# gemini.net
KiCad netlist of a schematic drawn in EAGLE
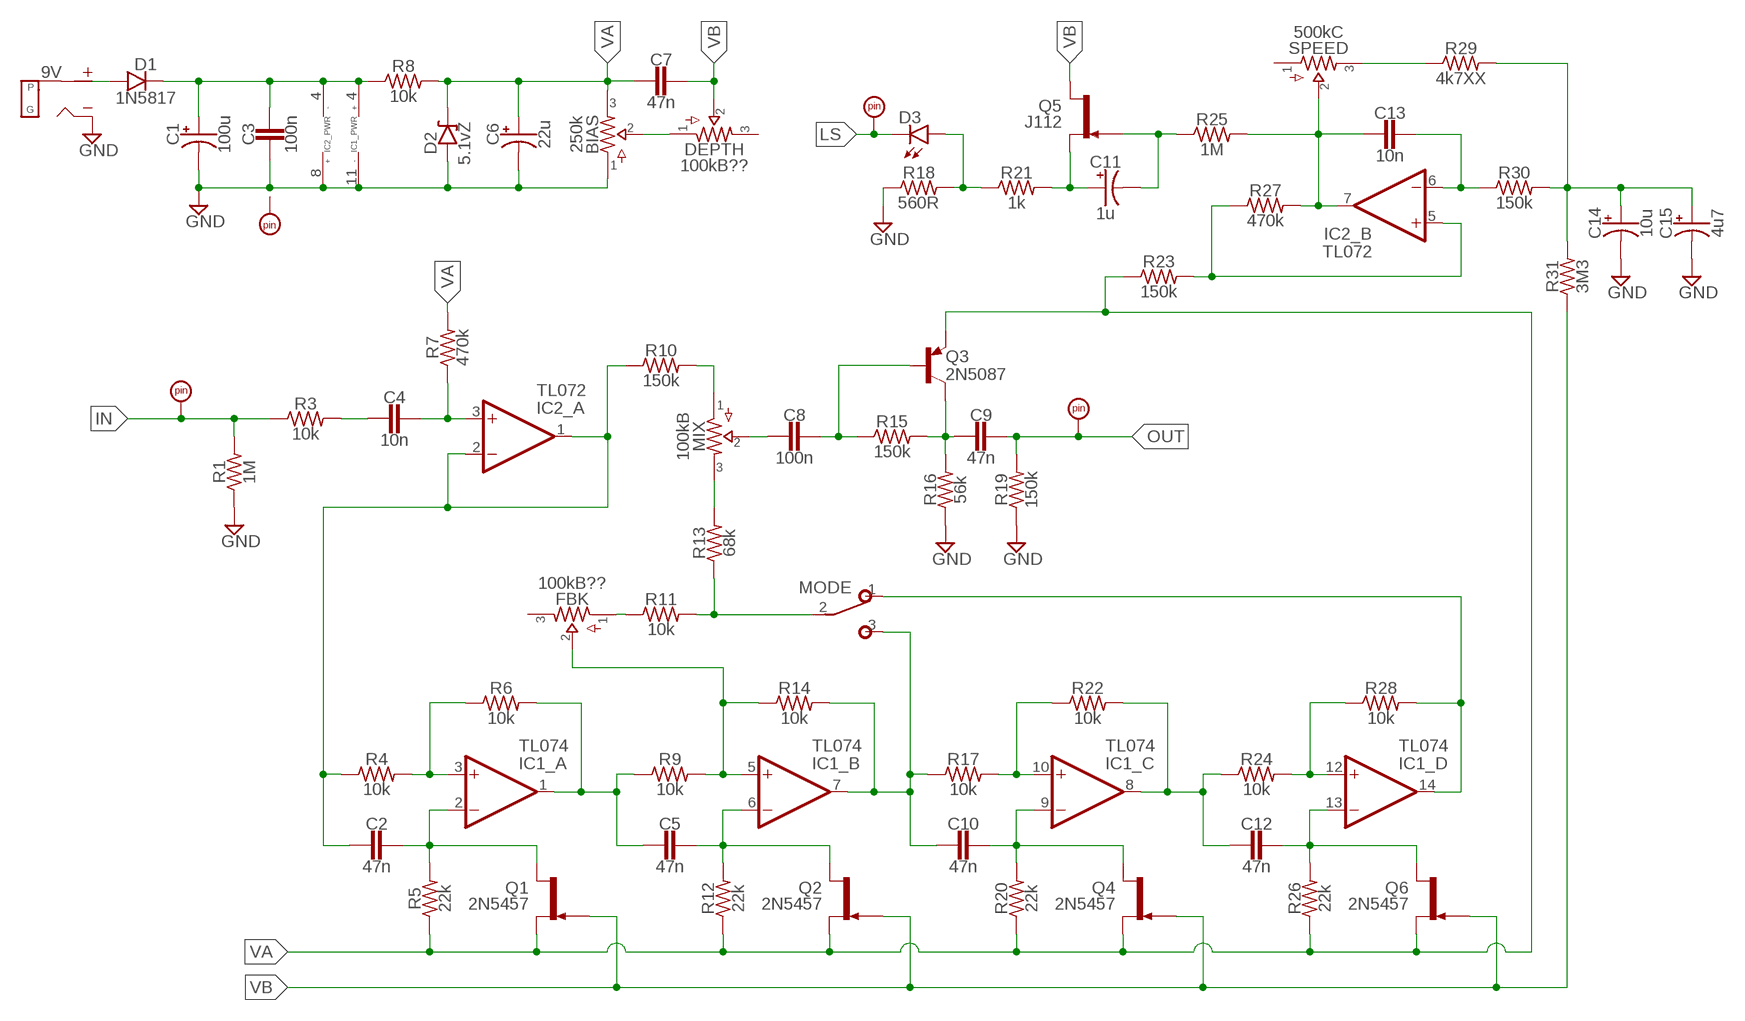
[diagram p0: schematic, sheet 1]

(export (version "E")
  (design (tool "Eeschema 10.0.6"))
  (components
    (comp (ref "9V")
      (value "DC_MONO")
      (footprint "eagle-import:DC")
      (libsource (lib "eagle-import") (part "DC_MONO"))
    )
    (comp (ref "BIAS")
      (value "250k")
      (footprint "eagle-import:2262_TRIM")
      (libsource (lib "eagle-import") (part "POTSTRIM"))
    )
    (comp (ref "C1")
      (value "100u")
      (footprint "eagle-import:050_020_1")
      (libsource (lib "eagle-import") (part "0501"))
    )
    (comp (ref "C2")
      (value "47n")
      (footprint "eagle-import:050X030_025_2")
      (libsource (lib "eagle-import") (part "CER/FILM2"))
    )
    (comp (ref "C3")
      (value "100n")
      (footprint "eagle-import:050X030_025_2")
      (libsource (lib "eagle-import") (part "CER/FILM2"))
    )
    (comp (ref "C4")
      (value "10n")
      (footprint "eagle-import:050X030_025_2")
      (libsource (lib "eagle-import") (part "CER/FILM2"))
    )
    (comp (ref "C5")
      (value "47n")
      (footprint "eagle-import:050X030_025_2")
      (libsource (lib "eagle-import") (part "CER/FILM2"))
    )
    (comp (ref "C6")
      (value "22u")
      (footprint "eagle-import:050_020_1")
      (libsource (lib "eagle-import") (part "0501"))
    )
    (comp (ref "C7")
      (value "47n")
      (footprint "eagle-import:050X030_025_2")
      (libsource (lib "eagle-import") (part "CER/FILM2"))
    )
    (comp (ref "C8")
      (value "100n")
      (footprint "eagle-import:050X030_025_2")
      (libsource (lib "eagle-import") (part "CER/FILM2"))
    )
    (comp (ref "C9")
      (value "47n")
      (footprint "eagle-import:050X030_025_2")
      (libsource (lib "eagle-import") (part "CER/FILM2"))
    )
    (comp (ref "C10")
      (value "47n")
      (footprint "eagle-import:050X030_025_2")
      (libsource (lib "eagle-import") (part "CER/FILM2"))
    )
    (comp (ref "C11")
      (value "1u")
      (footprint "eagle-import:050_020_1")
      (libsource (lib "eagle-import") (part "0501"))
    )
    (comp (ref "C12")
      (value "47n")
      (footprint "eagle-import:050X030_025_2")
      (libsource (lib "eagle-import") (part "CER/FILM2"))
    )
    (comp (ref "C13")
      (value "10n")
      (footprint "eagle-import:050X030_025_2")
      (libsource (lib "eagle-import") (part "CER/FILM2"))
    )
    (comp (ref "C14")
      (value "10u")
      (footprint "eagle-import:050_020_1")
      (libsource (lib "eagle-import") (part "0501"))
    )
    (comp (ref "C15")
      (value "4u7")
      (footprint "eagle-import:050_020_1")
      (libsource (lib "eagle-import") (part "0501"))
    )
    (comp (ref "D1")
      (value "1N5817")
      (footprint "eagle-import:DO41-2")
      (libsource (lib "eagle-import") (part "DO41.2"))
    )
    (comp (ref "D2")
      (value "5.1vZ")
      (footprint "eagle-import:DO41-3")
      (libsource (lib "eagle-import") (part "ZENER.3"))
    )
    (comp (ref "D3")
      (value "LEDA")
      (footprint "eagle-import:3MM_A")
      (libsource (lib "eagle-import") (part "LEDA"))
    )
    (comp (ref "DEPTH")
      (value "100kB??")
      (footprint "eagle-import:16MM")
      (libsource (lib "eagle-import") (part "POTS16MM"))
    )
    (comp (ref "FBK")
      (value "100kB??")
      (footprint "eagle-import:16MM")
      (libsource (lib "eagle-import") (part "POTS16MM"))
    )
    (comp (ref "GND")
      (value "PADRND")
      (footprint "eagle-import:ROUND")
      (libsource (lib "eagle-import") (part "PADRND"))
    )
    (comp (ref "IC1")
      (value "TL074")
      (footprint "eagle-import:DIL14")
      (libsource (lib "eagle-import") (part "QUADTH"))
    )
    (comp (ref "IC2")
      (value "TL072")
      (footprint "eagle-import:DIL08")
      (libsource (lib "eagle-import") (part "DUALTH"))
    )
    (comp (ref "IN")
      (value "PADSQR")
      (footprint "eagle-import:SQUARE")
      (libsource (lib "eagle-import") (part "PADSQR"))
    )
    (comp (ref "MIX")
      (value "100kB")
      (footprint "eagle-import:16MM")
      (libsource (lib "eagle-import") (part "POTS16MM"))
    )
    (comp (ref "MODE")
      (value "SPDTPADS")
      (footprint "eagle-import:SPDT")
      (libsource (lib "eagle-import") (part "SPDTPADS"))
    )
    (comp (ref "OUT")
      (value "PADSQR")
      (footprint "eagle-import:SQUARE")
      (libsource (lib "eagle-import") (part "PADSQR"))
    )
    (comp (ref "PAD3")
      (value "PADRND")
      (footprint "eagle-import:ROUND")
      (libsource (lib "eagle-import") (part "PADRND"))
    )
    (comp (ref "Q1")
      (value "2N5457")
      (footprint "eagle-import:TO92-")
      (libsource (lib "eagle-import") (part "2N5457"))
    )
    (comp (ref "Q2")
      (value "2N5457")
      (footprint "eagle-import:TO92-")
      (libsource (lib "eagle-import") (part "2N5457"))
    )
    (comp (ref "Q3")
      (value "2N5087")
      (footprint "eagle-import:TO92-")
      (libsource (lib "eagle-import") (part "2N5087.1"))
    )
    (comp (ref "Q4")
      (value "2N5457")
      (footprint "eagle-import:TO92-")
      (libsource (lib "eagle-import") (part "2N5457"))
    )
    (comp (ref "Q5")
      (value "J112")
      (footprint "eagle-import:TO92-")
      (libsource (lib "eagle-import") (part "J201"))
    )
    (comp (ref "Q6")
      (value "2N5457")
      (footprint "eagle-import:TO92-")
      (libsource (lib "eagle-import") (part "2N5457"))
    )
    (comp (ref "R1")
      (value "1M")
      (footprint "eagle-import:R0207_3")
      (libsource (lib "eagle-import") (part "R_.3B"))
    )
    (comp (ref "R3")
      (value "10k")
      (footprint "eagle-import:R0207_3")
      (libsource (lib "eagle-import") (part "R_.3B"))
    )
    (comp (ref "R4")
      (value "10k")
      (footprint "eagle-import:R0207_3")
      (libsource (lib "eagle-import") (part "R_.3B"))
    )
    (comp (ref "R5")
      (value "22k")
      (footprint "eagle-import:R0207_3")
      (libsource (lib "eagle-import") (part "R_.3B"))
    )
    (comp (ref "R6")
      (value "10k")
      (footprint "eagle-import:R0207_3")
      (libsource (lib "eagle-import") (part "R_.3B"))
    )
    (comp (ref "R7")
      (value "470k")
      (footprint "eagle-import:R0207_3")
      (libsource (lib "eagle-import") (part "R_.3B"))
    )
    (comp (ref "R8")
      (value "10k")
      (footprint "eagle-import:R0207_3")
      (libsource (lib "eagle-import") (part "R_.3B"))
    )
    (comp (ref "R9")
      (value "10k")
      (footprint "eagle-import:R0207_3")
      (libsource (lib "eagle-import") (part "R_.3B"))
    )
    (comp (ref "R10")
      (value "150k")
      (footprint "eagle-import:R0207_3")
      (libsource (lib "eagle-import") (part "R_.3B"))
    )
    (comp (ref "R11")
      (value "10k")
      (footprint "eagle-import:R0207_3")
      (libsource (lib "eagle-import") (part "R_.3B"))
    )
    (comp (ref "R12")
      (value "22k")
      (footprint "eagle-import:R0207_3")
      (libsource (lib "eagle-import") (part "R_.3B"))
    )
    (comp (ref "R13")
      (value "68k")
      (footprint "eagle-import:R0207_3")
      (libsource (lib "eagle-import") (part "R_.3B"))
    )
    (comp (ref "R14")
      (value "10k")
      (footprint "eagle-import:R0207_3")
      (libsource (lib "eagle-import") (part "R_.3B"))
    )
    (comp (ref "R15")
      (value "150k")
      (footprint "eagle-import:R0207_3")
      (libsource (lib "eagle-import") (part "R_.3B"))
    )
    (comp (ref "R16")
      (value "56k")
      (footprint "eagle-import:R0207_3")
      (libsource (lib "eagle-import") (part "R_.3B"))
    )
    (comp (ref "R17")
      (value "10k")
      (footprint "eagle-import:R0207_3")
      (libsource (lib "eagle-import") (part "R_.3B"))
    )
    (comp (ref "R18")
      (value "560R")
      (footprint "eagle-import:R0207_3")
      (libsource (lib "eagle-import") (part "R_.3B"))
    )
    (comp (ref "R19")
      (value "150k")
      (footprint "eagle-import:R0207_3")
      (libsource (lib "eagle-import") (part "R_.3B"))
    )
    (comp (ref "R20")
      (value "22k")
      (footprint "eagle-import:R0207_3")
      (libsource (lib "eagle-import") (part "R_.3B"))
    )
    (comp (ref "R21")
      (value "1k")
      (footprint "eagle-import:R0207_3")
      (libsource (lib "eagle-import") (part "R_.3B"))
    )
    (comp (ref "R22")
      (value "10k")
      (footprint "eagle-import:R0207_3")
      (libsource (lib "eagle-import") (part "R_.3B"))
    )
    (comp (ref "R23")
      (value "150k")
      (footprint "eagle-import:R0207_3")
      (libsource (lib "eagle-import") (part "R_.3B"))
    )
    (comp (ref "R24")
      (value "10k")
      (footprint "eagle-import:R0207_3")
      (libsource (lib "eagle-import") (part "R_.3B"))
    )
    (comp (ref "R25")
      (value "1M")
      (footprint "eagle-import:R0207_3")
      (libsource (lib "eagle-import") (part "R_.3B"))
    )
    (comp (ref "R26")
      (value "22k")
      (footprint "eagle-import:R0207_3")
      (libsource (lib "eagle-import") (part "R_.3B"))
    )
    (comp (ref "R27")
      (value "470k")
      (footprint "eagle-import:R0207_3")
      (libsource (lib "eagle-import") (part "R_.3B"))
    )
    (comp (ref "R28")
      (value "10k")
      (footprint "eagle-import:R0207_3")
      (libsource (lib "eagle-import") (part "R_.3B"))
    )
    (comp (ref "R29")
      (value "4k7XX")
      (footprint "eagle-import:R0207_3")
      (libsource (lib "eagle-import") (part "R_.3B"))
    )
    (comp (ref "R30")
      (value "150k")
      (footprint "eagle-import:R0207_3")
      (libsource (lib "eagle-import") (part "R_.3B"))
    )
    (comp (ref "R31")
      (value "3M3")
      (footprint "eagle-import:R0207_3")
      (libsource (lib "eagle-import") (part "R_.3B"))
    )
    (comp (ref "SPEED")
      (value "500kC")
      (footprint "eagle-import:16MM")
      (libsource (lib "eagle-import") (part "POTS16MM"))
    )
  )
  (nets
    (net (code "1") (name "GND") (class "Default")
      (node (ref "9V") (pin "S") (pinfunction "SLEEVE_S") (pintype "passive"))
      (node (ref "BIAS") (pin "1") (pinfunction "1_1") (pintype "passive"))
      (node (ref "C1") (pin "-") (pinfunction "-_-") (pintype "passive"))
      (node (ref "C14") (pin "-") (pinfunction "-_-") (pintype "passive"))
      (node (ref "C15") (pin "-") (pinfunction "-_-") (pintype "passive"))
      (node (ref "C3") (pin "2") (pinfunction "2_2") (pintype "passive"))
      (node (ref "C6") (pin "-") (pinfunction "-_-") (pintype "passive"))
      (node (ref "D2") (pin "A") (pinfunction "A_A") (pintype "passive"))
      (node (ref "IC1") (pin "11") (pinfunction "V-_11") (pintype "power_in"))
      (node (ref "IC2") (pin "8") (pinfunction "V+_8") (pintype "power_in"))
      (node (ref "R1") (pin "1") (pinfunction "1_1") (pintype "passive"))
      (node (ref "R16") (pin "1") (pinfunction "1_1") (pintype "passive"))
      (node (ref "R18") (pin "1") (pinfunction "1_1") (pintype "passive"))
      (node (ref "R19") (pin "1") (pinfunction "1_1") (pintype "passive"))
    )
    (net (code "2") (name "IN") (class "Default")
      (node (ref "IN") (pin "1") (pinfunction "P$1_1") (pintype "bidirectional"))
      (node (ref "R1") (pin "2") (pinfunction "2_2") (pintype "passive"))
      (node (ref "R3") (pin "1") (pinfunction "1_1") (pintype "passive"))
    )
    (net (code "3") (name "LS") (class "Default")
      (node (ref "D3") (pin "K") (pinfunction "C_K") (pintype "passive"))
      (node (ref "PAD3") (pin "1") (pinfunction "P$1_1") (pintype "bidirectional"))
    )
    (net (code "4") (name "Net-(9V-TIP)") (class "Default")
      (node (ref "9V") (pin "T") (pinfunction "TIP_T") (pintype "passive"))
      (node (ref "D1") (pin "A") (pinfunction "A_A") (pintype "passive"))
    )
    (net (code "5") (name "Net-(BIAS-Pad2)") (class "Default")
      (node (ref "BIAS") (pin "2") (pinfunction "2_2") (pintype "passive"))
      (node (ref "DEPTH") (pin "1") (pinfunction "1_1") (pintype "passive"))
    )
    (net (code "6") (name "Net-(C4-Pad2)") (class "Default")
      (node (ref "C4") (pin "2") (pinfunction "2_2") (pintype "passive"))
      (node (ref "R3") (pin "2") (pinfunction "2_2") (pintype "passive"))
    )
    (net (code "7") (name "Net-(C8-Pad2)") (class "Default")
      (node (ref "C8") (pin "2") (pinfunction "2_2") (pintype "passive"))
      (node (ref "MIX") (pin "2") (pinfunction "2_2") (pintype "passive"))
    )
    (net (code "8") (name "Net-(C14-Pad+)") (class "Default")
      (node (ref "C14") (pin "+") (pinfunction "+_+") (pintype "passive"))
      (node (ref "C15") (pin "+") (pinfunction "+_+") (pintype "passive"))
      (node (ref "R29") (pin "2") (pinfunction "2_2") (pintype "passive"))
      (node (ref "R30") (pin "2") (pinfunction "2_2") (pintype "passive"))
      (node (ref "R31") (pin "2") (pinfunction "2_2") (pintype "passive"))
    )
    (net (code "9") (name "Net-(D3-PadA)") (class "Default")
      (node (ref "D3") (pin "A") (pinfunction "A_A") (pintype "passive"))
      (node (ref "R18") (pin "2") (pinfunction "2_2") (pintype "passive"))
      (node (ref "R21") (pin "1") (pinfunction "1_1") (pintype "passive"))
    )
    (net (code "10") (name "Net-(FBK-Pad1)") (class "Default")
      (node (ref "FBK") (pin "1") (pinfunction "1_1") (pintype "passive"))
      (node (ref "R11") (pin "1") (pinfunction "1_1") (pintype "passive"))
    )
    (net (code "11") (name "Net-(IC1A-+IN)") (class "Default")
      (node (ref "IC1") (pin "3") (pinfunction "+IN_3") (pintype "input"))
      (node (ref "R4") (pin "2") (pinfunction "2_2") (pintype "passive"))
      (node (ref "R6") (pin "1") (pinfunction "1_1") (pintype "passive"))
    )
    (net (code "12") (name "Net-(IC1A--IN)") (class "Default")
      (node (ref "C2") (pin "1") (pinfunction "1_1") (pintype "passive"))
      (node (ref "IC1") (pin "2") (pinfunction "-IN_2") (pintype "input"))
      (node (ref "Q1") (pin "3") (pinfunction "D_3") (pintype "passive"))
      (node (ref "R5") (pin "2") (pinfunction "2_2") (pintype "passive"))
    )
    (net (code "13") (name "Net-(IC1A-OUT)") (class "Default")
      (node (ref "C5") (pin "2") (pinfunction "2_2") (pintype "passive"))
      (node (ref "IC1") (pin "1") (pinfunction "OUT_1") (pintype "output"))
      (node (ref "R6") (pin "2") (pinfunction "2_2") (pintype "passive"))
      (node (ref "R9") (pin "1") (pinfunction "1_1") (pintype "passive"))
    )
    (net (code "14") (name "Net-(IC1B-+IN)") (class "Default")
      (node (ref "FBK") (pin "2") (pinfunction "2_2") (pintype "passive"))
      (node (ref "IC1") (pin "5") (pinfunction "+IN_5") (pintype "input"))
      (node (ref "R14") (pin "1") (pinfunction "1_1") (pintype "passive"))
      (node (ref "R9") (pin "2") (pinfunction "2_2") (pintype "passive"))
    )
    (net (code "15") (name "Net-(IC1B--IN)") (class "Default")
      (node (ref "C5") (pin "1") (pinfunction "1_1") (pintype "passive"))
      (node (ref "IC1") (pin "6") (pinfunction "-IN_6") (pintype "input"))
      (node (ref "Q2") (pin "3") (pinfunction "D_3") (pintype "passive"))
      (node (ref "R12") (pin "2") (pinfunction "2_2") (pintype "passive"))
    )
    (net (code "16") (name "Net-(IC1B-OUT)") (class "Default")
      (node (ref "C10") (pin "2") (pinfunction "2_2") (pintype "passive"))
      (node (ref "IC1") (pin "7") (pinfunction "OUT_7") (pintype "output"))
      (node (ref "MODE") (pin "3") (pinfunction "S_3") (pintype "passive"))
      (node (ref "R14") (pin "2") (pinfunction "2_2") (pintype "passive"))
      (node (ref "R17") (pin "1") (pinfunction "1_1") (pintype "passive"))
    )
    (net (code "17") (name "Net-(IC1C-+IN)") (class "Default")
      (node (ref "IC1") (pin "10") (pinfunction "+IN_10") (pintype "input"))
      (node (ref "R17") (pin "2") (pinfunction "2_2") (pintype "passive"))
      (node (ref "R22") (pin "1") (pinfunction "1_1") (pintype "passive"))
    )
    (net (code "18") (name "Net-(IC1C--IN)") (class "Default")
      (node (ref "C10") (pin "1") (pinfunction "1_1") (pintype "passive"))
      (node (ref "IC1") (pin "9") (pinfunction "-IN_9") (pintype "input"))
      (node (ref "Q4") (pin "3") (pinfunction "D_3") (pintype "passive"))
      (node (ref "R20") (pin "2") (pinfunction "2_2") (pintype "passive"))
    )
    (net (code "19") (name "Net-(IC1C-OUT)") (class "Default")
      (node (ref "C12") (pin "2") (pinfunction "2_2") (pintype "passive"))
      (node (ref "IC1") (pin "8") (pinfunction "OUT_8") (pintype "output"))
      (node (ref "R22") (pin "2") (pinfunction "2_2") (pintype "passive"))
      (node (ref "R24") (pin "1") (pinfunction "1_1") (pintype "passive"))
    )
    (net (code "20") (name "Net-(IC1D-+IN)") (class "Default")
      (node (ref "IC1") (pin "12") (pinfunction "+IN_12") (pintype "input"))
      (node (ref "R24") (pin "2") (pinfunction "2_2") (pintype "passive"))
      (node (ref "R28") (pin "1") (pinfunction "1_1") (pintype "passive"))
    )
    (net (code "21") (name "Net-(IC1D--IN)") (class "Default")
      (node (ref "C12") (pin "1") (pinfunction "1_1") (pintype "passive"))
      (node (ref "IC1") (pin "13") (pinfunction "-IN_13") (pintype "input"))
      (node (ref "Q6") (pin "3") (pinfunction "D_3") (pintype "passive"))
      (node (ref "R26") (pin "2") (pinfunction "2_2") (pintype "passive"))
    )
    (net (code "22") (name "Net-(IC1D-OUT)") (class "Default")
      (node (ref "IC1") (pin "14") (pinfunction "OUT_14") (pintype "output"))
      (node (ref "MODE") (pin "1") (pinfunction "O_1") (pintype "passive"))
      (node (ref "R28") (pin "2") (pinfunction "2_2") (pintype "passive"))
    )
    (net (code "23") (name "Net-(IC1E-V+)") (class "Default")
      (node (ref "C1") (pin "+") (pinfunction "+_+") (pintype "passive"))
      (node (ref "C3") (pin "1") (pinfunction "1_1") (pintype "passive"))
      (node (ref "D1") (pin "C") (pinfunction "C_C") (pintype "passive"))
      (node (ref "IC1") (pin "4") (pinfunction "V+_4") (pintype "power_in"))
      (node (ref "IC2") (pin "4") (pinfunction "V-_4") (pintype "power_in"))
      (node (ref "R8") (pin "1") (pinfunction "1_1") (pintype "passive"))
    )
    (net (code "24") (name "Net-(IC2A-+IN)") (class "Default")
      (node (ref "C4") (pin "1") (pinfunction "1_1") (pintype "passive"))
      (node (ref "IC2") (pin "3") (pinfunction "+IN_3") (pintype "input"))
      (node (ref "R7") (pin "1") (pinfunction "1_1") (pintype "passive"))
    )
    (net (code "25") (name "Net-(IC2A--IN)") (class "Default")
      (node (ref "C2") (pin "2") (pinfunction "2_2") (pintype "passive"))
      (node (ref "IC2") (pin "1") (pinfunction "OUT_1") (pintype "output"))
      (node (ref "IC2") (pin "2") (pinfunction "-IN_2") (pintype "input"))
      (node (ref "R10") (pin "1") (pinfunction "1_1") (pintype "passive"))
      (node (ref "R4") (pin "1") (pinfunction "1_1") (pintype "passive"))
    )
    (net (code "26") (name "Net-(IC2B-+IN)") (class "Default")
      (node (ref "IC2") (pin "5") (pinfunction "+IN_5") (pintype "input"))
      (node (ref "R23") (pin "2") (pinfunction "2_2") (pintype "passive"))
      (node (ref "R27") (pin "1") (pinfunction "1_1") (pintype "passive"))
    )
    (net (code "27") (name "Net-(IC2B--IN)") (class "Default")
      (node (ref "C13") (pin "1") (pinfunction "1_1") (pintype "passive"))
      (node (ref "IC2") (pin "6") (pinfunction "-IN_6") (pintype "input"))
      (node (ref "R30") (pin "1") (pinfunction "1_1") (pintype "passive"))
    )
    (net (code "28") (name "Net-(IC2B-OUT)") (class "Default")
      (node (ref "C13") (pin "2") (pinfunction "2_2") (pintype "passive"))
      (node (ref "IC2") (pin "7") (pinfunction "OUT_7") (pintype "output"))
      (node (ref "R25") (pin "2") (pinfunction "2_2") (pintype "passive"))
      (node (ref "R27") (pin "2") (pinfunction "2_2") (pintype "passive"))
      (node (ref "SPEED") (pin "2") (pinfunction "2_2") (pintype "passive"))
    )
    (net (code "29") (name "Net-(MIX-Pad1)") (class "Default")
      (node (ref "MIX") (pin "1") (pinfunction "1_1") (pintype "passive"))
      (node (ref "R10") (pin "2") (pinfunction "2_2") (pintype "passive"))
    )
    (net (code "30") (name "Net-(MIX-Pad3)") (class "Default")
      (node (ref "MIX") (pin "3") (pinfunction "3_3") (pintype "passive"))
      (node (ref "R13") (pin "2") (pinfunction "2_2") (pintype "passive"))
    )
    (net (code "31") (name "Net-(MODE-P)") (class "Default")
      (node (ref "MODE") (pin "2") (pinfunction "P_2") (pintype "passive"))
      (node (ref "R11") (pin "2") (pinfunction "2_2") (pintype "passive"))
      (node (ref "R13") (pin "1") (pinfunction "1_1") (pintype "passive"))
    )
    (net (code "32") (name "Net-(Q3-B)") (class "Default")
      (node (ref "C8") (pin "1") (pinfunction "1_1") (pintype "passive"))
      (node (ref "Q3") (pin "2") (pinfunction "B_2") (pintype "passive"))
      (node (ref "R15") (pin "1") (pinfunction "1_1") (pintype "passive"))
    )
    (net (code "33") (name "Net-(Q3-C)") (class "Default")
      (node (ref "C9") (pin "2") (pinfunction "2_2") (pintype "passive"))
      (node (ref "Q3") (pin "1") (pinfunction "C_1") (pintype "passive"))
      (node (ref "R15") (pin "2") (pinfunction "2_2") (pintype "passive"))
      (node (ref "R16") (pin "2") (pinfunction "2_2") (pintype "passive"))
    )
    (net (code "34") (name "Net-(Q5-G)") (class "Default")
      (node (ref "C11") (pin "-") (pinfunction "-_-") (pintype "passive"))
      (node (ref "Q5") (pin "1") (pinfunction "G_1") (pintype "passive"))
      (node (ref "R25") (pin "1") (pinfunction "1_1") (pintype "passive"))
    )
    (net (code "35") (name "Net-(Q5-S)") (class "Default")
      (node (ref "C11") (pin "+") (pinfunction "+_+") (pintype "passive"))
      (node (ref "Q5") (pin "2") (pinfunction "S_2") (pintype "passive"))
      (node (ref "R21") (pin "2") (pinfunction "2_2") (pintype "passive"))
    )
    (net (code "36") (name "Net-(R29-Pad1)") (class "Default")
      (node (ref "R29") (pin "1") (pinfunction "1_1") (pintype "passive"))
      (node (ref "SPEED") (pin "3") (pinfunction "3_3") (pintype "passive"))
    )
    (net (code "37") (name "OUT") (class "Default")
      (node (ref "C9") (pin "1") (pinfunction "1_1") (pintype "passive"))
      (node (ref "OUT") (pin "1") (pinfunction "P$1_1") (pintype "bidirectional"))
      (node (ref "R19") (pin "2") (pinfunction "2_2") (pintype "passive"))
    )
    (net (code "38") (name "VA") (class "Default")
      (node (ref "BIAS") (pin "3") (pinfunction "3_3") (pintype "passive"))
      (node (ref "C6") (pin "+") (pinfunction "+_+") (pintype "passive"))
      (node (ref "C7") (pin "2") (pinfunction "2_2") (pintype "passive"))
      (node (ref "D2") (pin "C") (pinfunction "C_C") (pintype "passive"))
      (node (ref "Q1") (pin "2") (pinfunction "S_2") (pintype "passive"))
      (node (ref "Q2") (pin "2") (pinfunction "S_2") (pintype "passive"))
      (node (ref "Q3") (pin "3") (pinfunction "E_3") (pintype "passive"))
      (node (ref "Q4") (pin "2") (pinfunction "S_2") (pintype "passive"))
      (node (ref "Q6") (pin "2") (pinfunction "S_2") (pintype "passive"))
      (node (ref "R12") (pin "1") (pinfunction "1_1") (pintype "passive"))
      (node (ref "R20") (pin "1") (pinfunction "1_1") (pintype "passive"))
      (node (ref "R23") (pin "1") (pinfunction "1_1") (pintype "passive"))
      (node (ref "R26") (pin "1") (pinfunction "1_1") (pintype "passive"))
      (node (ref "R5") (pin "1") (pinfunction "1_1") (pintype "passive"))
      (node (ref "R7") (pin "2") (pinfunction "2_2") (pintype "passive"))
      (node (ref "R8") (pin "2") (pinfunction "2_2") (pintype "passive"))
    )
    (net (code "39") (name "VB") (class "Default")
      (node (ref "C7") (pin "1") (pinfunction "1_1") (pintype "passive"))
      (node (ref "DEPTH") (pin "2") (pinfunction "2_2") (pintype "passive"))
      (node (ref "Q1") (pin "1") (pinfunction "G_1") (pintype "passive"))
      (node (ref "Q2") (pin "1") (pinfunction "G_1") (pintype "passive"))
      (node (ref "Q4") (pin "1") (pinfunction "G_1") (pintype "passive"))
      (node (ref "Q5") (pin "3") (pinfunction "D_3") (pintype "passive"))
      (node (ref "Q6") (pin "1") (pinfunction "G_1") (pintype "passive"))
      (node (ref "R31") (pin "1") (pinfunction "1_1") (pintype "passive"))
    )
    (net (code "40") (name "unconnected-(DEPTH-Pad3)") (class "Default")
      (node (ref "DEPTH") (pin "3") (pinfunction "3_3") (pintype "passive"))
    )
    (net (code "41") (name "unconnected-(FBK-Pad3)") (class "Default")
      (node (ref "FBK") (pin "3") (pinfunction "3_3") (pintype "passive"))
    )
    (net (code "42") (name "unconnected-(GND-P$1-Pad1)") (class "Default")
      (node (ref "GND") (pin "1") (pinfunction "P$1_1") (pintype "bidirectional"))
    )
    (net (code "43") (name "unconnected-(SPEED-Pad1)") (class "Default")
      (node (ref "SPEED") (pin "1") (pinfunction "1_1") (pintype "passive"))
    )
  )
)
